# control_board.net
KiCad netlist of a schematic drawn in EAGLE
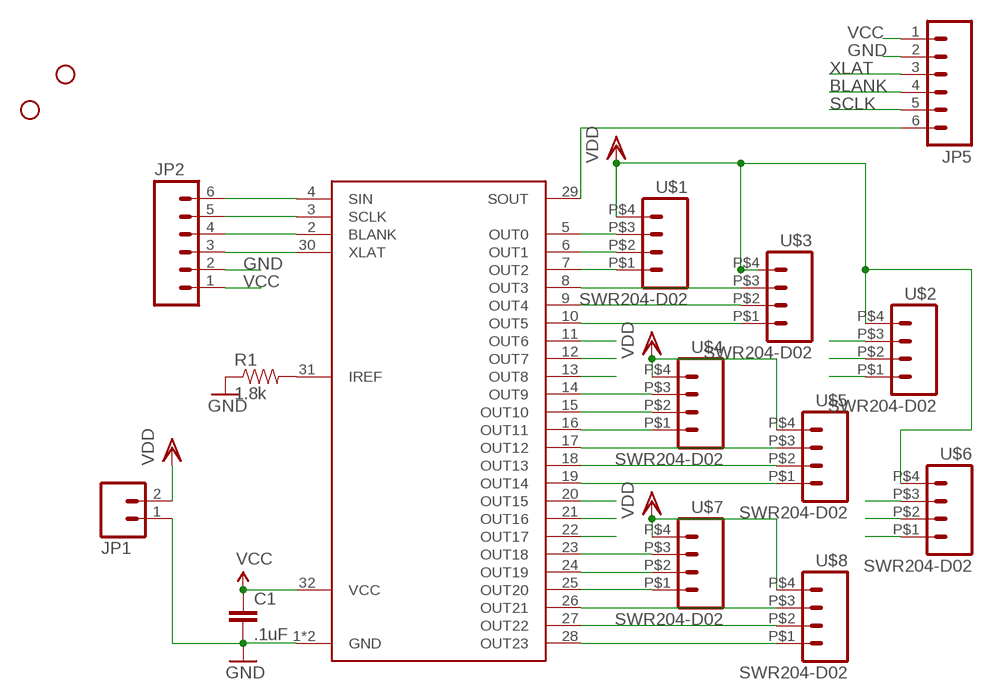
[diagram p0: schematic, sheet 1]

(export (version "E")
  (design (tool "Eeschema 10.0.6"))
  (components
    (comp (ref "C1")
      (value ".1uF")
      (footprint "eagle-import:0603-CAP")
      (libsource (lib "eagle-import") (part "CAP0603-CAP"))
    )
    (comp (ref "JP1")
      (value "M02-JST-2MM-SMT")
      (footprint "eagle-import:JST-2-SMD")
      (libsource (lib "eagle-import") (part "M02-JST-2MM-SMT"))
    )
    (comp (ref "JP2")
      (value "M06LOCK")
      (footprint "eagle-import:1X06_LOCK")
      (libsource (lib "eagle-import") (part "M06LOCK"))
    )
    (comp (ref "JP5")
      (value "M06LOCK")
      (footprint "eagle-import:1X06_LOCK")
      (libsource (lib "eagle-import") (part "M06LOCK"))
    )
    (comp (ref "R1")
      (value "1.8k")
      (footprint "eagle-import:0603-RES")
      (libsource (lib "eagle-import") (part "RESISTOR0603-RES"))
    )
    (comp (ref "STANDOFF2")
      (value "STAND-OFF")
      (footprint "eagle-import:STAND-OFF")
      (libsource (lib "eagle-import") (part "STAND-OFF"))
    )
    (comp (ref "STANDOFF3")
      (value "STAND-OFF")
      (footprint "eagle-import:STAND-OFF")
      (libsource (lib "eagle-import") (part "STAND-OFF"))
    )
    (comp (ref "TLC5947")
      (value "TLC5947DAP")
      (footprint "eagle-import:DAP")
      (libsource (lib "eagle-import") (part "TLC5947DAP"))
    )
    (comp (ref "U$1")
      (value "SWR204-D02")
      (footprint "eagle-import:SWR204")
      (libsource (lib "eagle-import") (part "SWR204-D02"))
    )
    (comp (ref "U$2")
      (value "SWR204-D02")
      (footprint "eagle-import:SWR204")
      (libsource (lib "eagle-import") (part "SWR204-D02"))
    )
    (comp (ref "U$3")
      (value "SWR204-D02")
      (footprint "eagle-import:SWR204")
      (libsource (lib "eagle-import") (part "SWR204-D02"))
    )
    (comp (ref "U$4")
      (value "SWR204-D02")
      (footprint "eagle-import:SWR204")
      (libsource (lib "eagle-import") (part "SWR204-D02"))
    )
    (comp (ref "U$5")
      (value "SWR204-D02")
      (footprint "eagle-import:SWR204")
      (libsource (lib "eagle-import") (part "SWR204-D02"))
    )
    (comp (ref "U$6")
      (value "SWR204-D02")
      (footprint "eagle-import:SWR204")
      (libsource (lib "eagle-import") (part "SWR204-D02"))
    )
    (comp (ref "U$7")
      (value "SWR204-D02")
      (footprint "eagle-import:SWR204")
      (libsource (lib "eagle-import") (part "SWR204-D02"))
    )
    (comp (ref "U$8")
      (value "SWR204-D02")
      (footprint "eagle-import:SWR204")
      (libsource (lib "eagle-import") (part "SWR204-D02"))
    )
  )
  (nets
    (net (code "1") (name "/BLANK") (class "Default")
      (node (ref "JP2") (pin "4") (pinfunction "4_4") (pintype "passive"))
      (node (ref "JP5") (pin "4") (pinfunction "4_4") (pintype "passive"))
      (node (ref "TLC5947") (pin "2") (pinfunction "BLANK_2") (pintype "bidirectional"))
    )
    (net (code "2") (name "/OUT6") (class "Default")
      (node (ref "TLC5947") (pin "11") (pinfunction "OUT6_11") (pintype "bidirectional"))
      (node (ref "U$2") (pin "P$3") (pinfunction "3_P$3") (pintype "passive"))
    )
    (net (code "3") (name "/OUT7") (class "Default")
      (node (ref "TLC5947") (pin "12") (pinfunction "OUT7_12") (pintype "bidirectional"))
      (node (ref "U$2") (pin "P$2") (pinfunction "2_P$2") (pintype "passive"))
    )
    (net (code "4") (name "/OUT8") (class "Default")
      (node (ref "TLC5947") (pin "13") (pinfunction "OUT8_13") (pintype "bidirectional"))
      (node (ref "U$2") (pin "P$1") (pinfunction "1_P$1") (pintype "passive"))
    )
    (net (code "5") (name "/OUT15") (class "Default")
      (node (ref "TLC5947") (pin "20") (pinfunction "OUT15_20") (pintype "bidirectional"))
      (node (ref "U$6") (pin "P$3") (pinfunction "3_P$3") (pintype "passive"))
    )
    (net (code "6") (name "/OUT16") (class "Default")
      (node (ref "TLC5947") (pin "21") (pinfunction "OUT16_21") (pintype "bidirectional"))
      (node (ref "U$6") (pin "P$2") (pinfunction "2_P$2") (pintype "passive"))
    )
    (net (code "7") (name "/OUT17") (class "Default")
      (node (ref "TLC5947") (pin "22") (pinfunction "OUT17_22") (pintype "bidirectional"))
      (node (ref "U$6") (pin "P$1") (pinfunction "1_P$1") (pintype "passive"))
    )
    (net (code "8") (name "/SCLK") (class "Default")
      (node (ref "JP2") (pin "5") (pinfunction "5_5") (pintype "passive"))
      (node (ref "JP5") (pin "5") (pinfunction "5_5") (pintype "passive"))
      (node (ref "TLC5947") (pin "3") (pinfunction "SCLK_3") (pintype "bidirectional"))
    )
    (net (code "9") (name "/XLAT") (class "Default")
      (node (ref "JP2") (pin "3") (pinfunction "3_3") (pintype "passive"))
      (node (ref "JP5") (pin "3") (pinfunction "3_3") (pintype "passive"))
      (node (ref "TLC5947") (pin "30") (pinfunction "XLAT_30") (pintype "bidirectional"))
    )
    (net (code "10") (name "GND") (class "Default")
      (node (ref "C1") (pin "2") (pinfunction "2_2") (pintype "passive"))
      (node (ref "JP1") (pin "1") (pinfunction "2_1") (pintype "passive"))
      (node (ref "JP2") (pin "2") (pinfunction "2_2") (pintype "passive"))
      (node (ref "JP5") (pin "2") (pinfunction "2_2") (pintype "passive"))
      (node (ref "R1") (pin "1") (pinfunction "1_1") (pintype "passive"))
      (node (ref "TLC5947") (pin "1") (pinfunction "GND_1") (pintype "bidirectional"))
      (node (ref "TLC5947") (pin "GND") (pinfunction "GND_GND") (pintype "bidirectional"))
    )
    (net (code "11") (name "Net-(TLC5947-IREF)") (class "Default")
      (node (ref "R1") (pin "2") (pinfunction "2_2") (pintype "passive"))
      (node (ref "TLC5947") (pin "31") (pinfunction "IREF_31") (pintype "bidirectional"))
    )
    (net (code "12") (name "Net-(TLC5947-OUT0)") (class "Default")
      (node (ref "TLC5947") (pin "5") (pinfunction "OUT0_5") (pintype "bidirectional"))
      (node (ref "U$1") (pin "P$3") (pinfunction "3_P$3") (pintype "passive"))
    )
    (net (code "13") (name "Net-(TLC5947-OUT1)") (class "Default")
      (node (ref "TLC5947") (pin "6") (pinfunction "OUT1_6") (pintype "bidirectional"))
      (node (ref "U$1") (pin "P$2") (pinfunction "2_P$2") (pintype "passive"))
    )
    (net (code "14") (name "Net-(TLC5947-OUT2)") (class "Default")
      (node (ref "TLC5947") (pin "7") (pinfunction "OUT2_7") (pintype "bidirectional"))
      (node (ref "U$1") (pin "P$1") (pinfunction "1_P$1") (pintype "passive"))
    )
    (net (code "15") (name "Net-(TLC5947-OUT3)") (class "Default")
      (node (ref "TLC5947") (pin "8") (pinfunction "OUT3_8") (pintype "bidirectional"))
      (node (ref "U$3") (pin "P$3") (pinfunction "3_P$3") (pintype "passive"))
    )
    (net (code "16") (name "Net-(TLC5947-OUT4)") (class "Default")
      (node (ref "TLC5947") (pin "9") (pinfunction "OUT4_9") (pintype "bidirectional"))
      (node (ref "U$3") (pin "P$2") (pinfunction "2_P$2") (pintype "passive"))
    )
    (net (code "17") (name "Net-(TLC5947-OUT5)") (class "Default")
      (node (ref "TLC5947") (pin "10") (pinfunction "OUT5_10") (pintype "bidirectional"))
      (node (ref "U$3") (pin "P$1") (pinfunction "1_P$1") (pintype "passive"))
    )
    (net (code "18") (name "Net-(TLC5947-OUT9)") (class "Default")
      (node (ref "TLC5947") (pin "14") (pinfunction "OUT9_14") (pintype "bidirectional"))
      (node (ref "U$4") (pin "P$3") (pinfunction "3_P$3") (pintype "passive"))
    )
    (net (code "19") (name "Net-(TLC5947-OUT10)") (class "Default")
      (node (ref "TLC5947") (pin "15") (pinfunction "OUT10_15") (pintype "bidirectional"))
      (node (ref "U$4") (pin "P$2") (pinfunction "2_P$2") (pintype "passive"))
    )
    (net (code "20") (name "Net-(TLC5947-OUT11)") (class "Default")
      (node (ref "TLC5947") (pin "16") (pinfunction "OUT11_16") (pintype "bidirectional"))
      (node (ref "U$4") (pin "P$1") (pinfunction "1_P$1") (pintype "passive"))
    )
    (net (code "21") (name "Net-(TLC5947-OUT12)") (class "Default")
      (node (ref "TLC5947") (pin "17") (pinfunction "OUT12_17") (pintype "bidirectional"))
      (node (ref "U$5") (pin "P$3") (pinfunction "3_P$3") (pintype "passive"))
    )
    (net (code "22") (name "Net-(TLC5947-OUT13)") (class "Default")
      (node (ref "TLC5947") (pin "18") (pinfunction "OUT13_18") (pintype "bidirectional"))
      (node (ref "U$5") (pin "P$2") (pinfunction "2_P$2") (pintype "passive"))
    )
    (net (code "23") (name "Net-(TLC5947-OUT14)") (class "Default")
      (node (ref "TLC5947") (pin "19") (pinfunction "OUT14_19") (pintype "bidirectional"))
      (node (ref "U$5") (pin "P$1") (pinfunction "1_P$1") (pintype "passive"))
    )
    (net (code "24") (name "Net-(TLC5947-OUT18)") (class "Default")
      (node (ref "TLC5947") (pin "23") (pinfunction "OUT18_23") (pintype "bidirectional"))
      (node (ref "U$7") (pin "P$3") (pinfunction "3_P$3") (pintype "passive"))
    )
    (net (code "25") (name "Net-(TLC5947-OUT19)") (class "Default")
      (node (ref "TLC5947") (pin "24") (pinfunction "OUT19_24") (pintype "bidirectional"))
      (node (ref "U$7") (pin "P$2") (pinfunction "2_P$2") (pintype "passive"))
    )
    (net (code "26") (name "Net-(TLC5947-OUT20)") (class "Default")
      (node (ref "TLC5947") (pin "25") (pinfunction "OUT20_25") (pintype "bidirectional"))
      (node (ref "U$7") (pin "P$1") (pinfunction "1_P$1") (pintype "passive"))
    )
    (net (code "27") (name "Net-(TLC5947-OUT21)") (class "Default")
      (node (ref "TLC5947") (pin "26") (pinfunction "OUT21_26") (pintype "bidirectional"))
      (node (ref "U$8") (pin "P$3") (pinfunction "3_P$3") (pintype "passive"))
    )
    (net (code "28") (name "Net-(TLC5947-OUT22)") (class "Default")
      (node (ref "TLC5947") (pin "27") (pinfunction "OUT22_27") (pintype "bidirectional"))
      (node (ref "U$8") (pin "P$2") (pinfunction "2_P$2") (pintype "passive"))
    )
    (net (code "29") (name "Net-(TLC5947-OUT23)") (class "Default")
      (node (ref "TLC5947") (pin "28") (pinfunction "OUT23_28") (pintype "bidirectional"))
      (node (ref "U$8") (pin "P$1") (pinfunction "1_P$1") (pintype "passive"))
    )
    (net (code "30") (name "Net-(TLC5947-SIN)") (class "Default")
      (node (ref "JP2") (pin "6") (pinfunction "6_6") (pintype "passive"))
      (node (ref "TLC5947") (pin "4") (pinfunction "SIN_4") (pintype "bidirectional"))
    )
    (net (code "31") (name "Net-(TLC5947-SOUT)") (class "Default")
      (node (ref "JP5") (pin "6") (pinfunction "6_6") (pintype "passive"))
      (node (ref "TLC5947") (pin "29") (pinfunction "SOUT_29") (pintype "bidirectional"))
    )
    (net (code "32") (name "VCC") (class "Default")
      (node (ref "C1") (pin "1") (pinfunction "1_1") (pintype "passive"))
      (node (ref "JP2") (pin "1") (pinfunction "1_1") (pintype "passive"))
      (node (ref "JP5") (pin "1") (pinfunction "1_1") (pintype "passive"))
      (node (ref "TLC5947") (pin "32") (pinfunction "VCC_32") (pintype "bidirectional"))
    )
    (net (code "33") (name "VDD") (class "Default")
      (node (ref "JP1") (pin "2") (pinfunction "1_2") (pintype "passive"))
      (node (ref "U$1") (pin "P$4") (pinfunction "4_P$4") (pintype "passive"))
      (node (ref "U$2") (pin "P$4") (pinfunction "4_P$4") (pintype "passive"))
      (node (ref "U$3") (pin "P$4") (pinfunction "4_P$4") (pintype "passive"))
      (node (ref "U$4") (pin "P$4") (pinfunction "4_P$4") (pintype "passive"))
      (node (ref "U$5") (pin "P$4") (pinfunction "4_P$4") (pintype "passive"))
      (node (ref "U$6") (pin "P$4") (pinfunction "4_P$4") (pintype "passive"))
      (node (ref "U$7") (pin "P$4") (pinfunction "4_P$4") (pintype "passive"))
      (node (ref "U$8") (pin "P$4") (pinfunction "4_P$4") (pintype "passive"))
    )
  )
)
